# schemat.net
KiCad netlist of a schematic drawn in Altium Designer
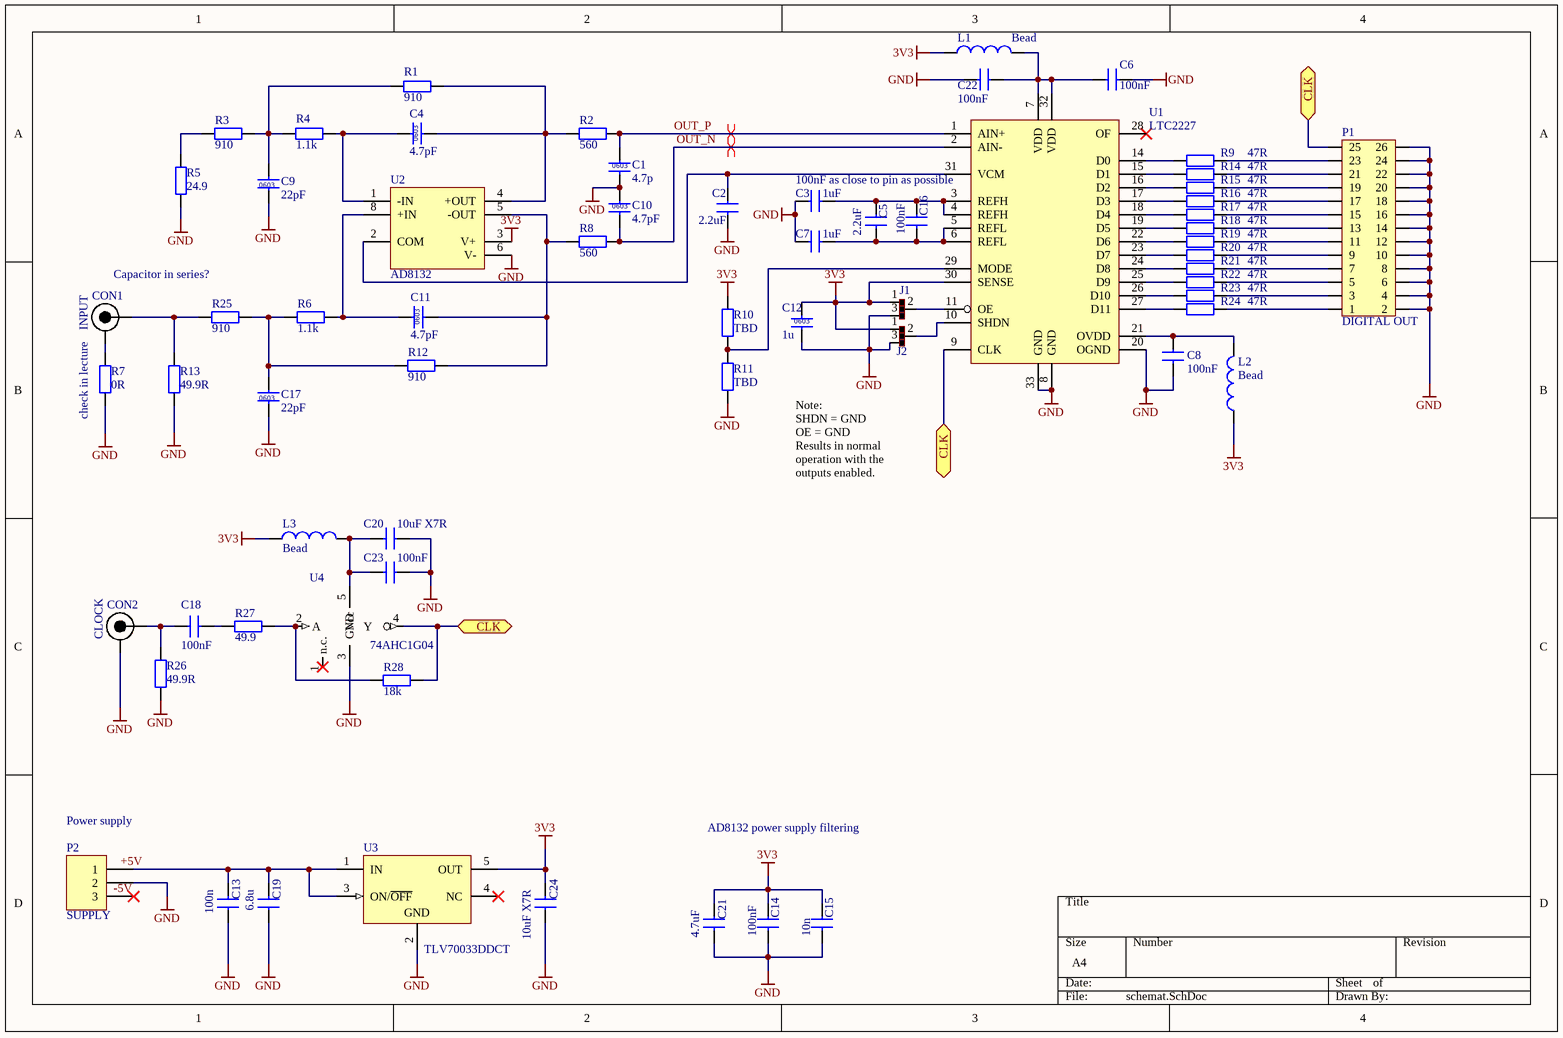
[diagram p0: schemat.SchDoc]

(export (version "E")
  (design (tool "Eeschema 10.0.6"))
  (components
    (comp (ref "C1")
      (value "4.7p")
      (footprint "0603")
      (fields (field (name "OBUDOWA") "0603"))
      (libsource (lib "iMX6") (part "Kondensator ceramiczny"))
    )
    (comp (ref "C2")
      (value "2.2uF")
      (footprint "0603")
      (libsource (lib "iMX6") (part "Kondensator ceramiczny"))
    )
    (comp (ref "C3")
      (value "1uF")
      (footprint "0603")
      (libsource (lib "iMX6") (part "Kondensator ceramiczny"))
    )
    (comp (ref "C4")
      (value "4.7pF")
      (footprint "0603")
      (fields (field (name "OBUDOWA") "0603"))
      (libsource (lib "iMX6") (part "Kondensator ceramiczny"))
    )
    (comp (ref "C5")
      (value "2.2uF")
      (footprint "0603")
      (libsource (lib "iMX6") (part "Kondensator ceramiczny"))
    )
    (comp (ref "C6")
      (value "100nF")
      (footprint "0603")
      (libsource (lib "iMX6") (part "Kondensator ceramiczny"))
    )
    (comp (ref "C7")
      (value "1uF")
      (footprint "0603")
      (libsource (lib "iMX6") (part "Kondensator ceramiczny"))
    )
    (comp (ref "C8")
      (value "100nF")
      (footprint "0603")
      (libsource (lib "iMX6") (part "Kondensator ceramiczny"))
    )
    (comp (ref "C9")
      (value "22pF")
      (footprint "0603")
      (fields (field (name "OBUDOWA") "0603"))
      (libsource (lib "iMX6") (part "Kondensator ceramiczny"))
    )
    (comp (ref "C10")
      (value "4.7pF")
      (footprint "0603")
      (fields (field (name "OBUDOWA") "0603"))
      (libsource (lib "iMX6") (part "Kondensator ceramiczny"))
    )
    (comp (ref "C11")
      (value "4.7pF")
      (footprint "0603")
      (fields (field (name "OBUDOWA") "0603"))
      (libsource (lib "iMX6") (part "Kondensator ceramiczny"))
    )
    (comp (ref "C12")
      (value "1u")
      (footprint "0603")
      (fields (field (name "OBUDOWA") "0603"))
      (libsource (lib "iMX6") (part "Kondensator ceramiczny"))
    )
    (comp (ref "C13")
      (value "100n")
      (footprint "0603")
      (libsource (lib "iMX6") (part "Kondensator ceramiczny"))
    )
    (comp (ref "C14")
      (value "100nF")
      (footprint "0603")
      (libsource (lib "iMX6") (part "Kondensator ceramiczny"))
    )
    (comp (ref "C15")
      (value "10n")
      (footprint "0603")
      (libsource (lib "iMX6") (part "Kondensator ceramiczny"))
    )
    (comp (ref "C16")
      (value "100nF")
      (footprint "0603")
      (libsource (lib "iMX6") (part "Kondensator ceramiczny"))
    )
    (comp (ref "C17")
      (value "22pF")
      (footprint "0603")
      (fields (field (name "OBUDOWA") "0603"))
      (libsource (lib "iMX6") (part "Kondensator ceramiczny"))
    )
    (comp (ref "C18")
      (value "100nF")
      (footprint "C0603")
      (libsource (lib "iMX6") (part "Kondensator ceramiczny"))
    )
    (comp (ref "C19")
      (value "6.8u")
      (footprint "0805")
      (libsource (lib "iMX6") (part "Kondensator ceramiczny"))
    )
    (comp (ref "C20")
      (value "10uF X7R")
      (footprint "0805")
      (libsource (lib "iMX6") (part "Kondensator ceramiczny"))
    )
    (comp (ref "C21")
      (value "4.7uF")
      (footprint "0603")
      (libsource (lib "iMX6") (part "Kondensator ceramiczny"))
    )
    (comp (ref "C22")
      (value "100nF")
      (footprint "0603")
      (libsource (lib "iMX6") (part "Kondensator ceramiczny"))
    )
    (comp (ref "C23")
      (value "100nF")
      (footprint "0603")
      (libsource (lib "iMX6") (part "Kondensator ceramiczny"))
    )
    (comp (ref "C24")
      (value "10uF X7R")
      (footprint "0805")
      (libsource (lib "iMX6") (part "Kondensator ceramiczny"))
    )
    (comp (ref "CON1") (value "INPUT") (footprint "SMA-16") (libsource (lib "A4WP") (part "SMA")))
    (comp (ref "CON2") (value "CLOCK") (footprint "SMA-16") (libsource (lib "A4WP") (part "SMA")))
    (comp (ref "J1") (value "ZW2/1") (footprint "ZW2/1") (libsource (lib "iMX6") (part "ZW2/1")))
    (comp (ref "J2") (value "ZW2/1") (footprint "ZW2/1") (libsource (lib "iMX6") (part "ZW2/1")))
    (comp (ref "L1")
      (value "Bead")
      (footprint "R0603")
      (description "Inductor")
      (fields (field (name "PUBLISHER") "Altium Limited"))
      (libsource (lib "Miscellaneous Devices") (part "Inductor"))
    )
    (comp (ref "L2")
      (value "Bead")
      (footprint "R0603")
      (description "Inductor")
      (fields (field (name "PUBLISHER") "Altium Limited"))
      (libsource (lib "Miscellaneous Devices") (part "Inductor"))
    )
    (comp (ref "L3")
      (value "Bead")
      (footprint "R0603")
      (description "Inductor")
      (fields (field (name "PUBLISHER") "Altium Limited"))
      (libsource (lib "Miscellaneous Devices") (part "Inductor"))
    )
    (comp (ref "P1")
      (value "DIGITAL OUT")
      (footprint "Header2x13")
      (libsource (lib "BibliotekiAltium") (part "Header2x13"))
    )
    (comp (ref "P2")
      (value "SUPPLY")
      (footprint "HDR1X3")
      (description "Header, 3-Pin")
      (fields (field (name "PUBLISHER") "Altium Limited"))
      (libsource (lib "Miscellaneous Connectors") (part "Header 3"))
    )
    (comp (ref "R1") (value "910") (footprint "0603") (libsource (lib "") (part "Rezystor_2")))
    (comp (ref "R2") (value "560") (footprint "0603") (libsource (lib "") (part "Rezystor_2")))
    (comp (ref "R3") (value "910") (footprint "0603") (libsource (lib "") (part "Rezystor_2")))
    (comp (ref "R4") (value "1.1k") (footprint "0603") (libsource (lib "") (part "Rezystor_2")))
    (comp (ref "R5") (value "24.9") (footprint "0603") (libsource (lib "") (part "Rezystor_1")))
    (comp (ref "R6") (value "1.1k") (footprint "0603") (libsource (lib "") (part "Rezystor_2")))
    (comp (ref "R7") (value "0R") (footprint "0603") (libsource (lib "") (part "Rezystor_1")))
    (comp (ref "R8") (value "560") (footprint "0603") (libsource (lib "") (part "Rezystor_2")))
    (comp (ref "R9") (value "47R") (footprint "0603") (libsource (lib "iMX6") (part "Rezystor")))
    (comp (ref "R10") (value "TBD") (footprint "0603") (libsource (lib "") (part "Rezystor_1")))
    (comp (ref "R11") (value "TBD") (footprint "0603") (libsource (lib "") (part "Rezystor_1")))
    (comp (ref "R12") (value "910") (footprint "0603CW") (libsource (lib "iMX6") (part "Rezystor")))
    (comp (ref "R13") (value "49.9R") (footprint "0603") (libsource (lib "") (part "Rezystor_1")))
    (comp (ref "R14") (value "47R") (footprint "0603") (libsource (lib "iMX6") (part "Rezystor")))
    (comp (ref "R15") (value "47R") (footprint "0603") (libsource (lib "iMX6") (part "Rezystor")))
    (comp (ref "R16") (value "47R") (footprint "0603") (libsource (lib "iMX6") (part "Rezystor")))
    (comp (ref "R17") (value "47R") (footprint "0603") (libsource (lib "iMX6") (part "Rezystor")))
    (comp (ref "R18") (value "47R") (footprint "0603") (libsource (lib "iMX6") (part "Rezystor")))
    (comp (ref "R19") (value "47R") (footprint "0603") (libsource (lib "iMX6") (part "Rezystor")))
    (comp (ref "R20") (value "47R") (footprint "0603") (libsource (lib "iMX6") (part "Rezystor")))
    (comp (ref "R21") (value "47R") (footprint "0603") (libsource (lib "iMX6") (part "Rezystor")))
    (comp (ref "R22") (value "47R") (footprint "0603") (libsource (lib "iMX6") (part "Rezystor")))
    (comp (ref "R23") (value "47R") (footprint "0603") (libsource (lib "iMX6") (part "Rezystor")))
    (comp (ref "R24") (value "47R") (footprint "0603") (libsource (lib "iMX6") (part "Rezystor")))
    (comp (ref "R25") (value "910") (footprint "0603") (libsource (lib "iMX6") (part "Rezystor")))
    (comp (ref "R26") (value "49.9R") (footprint "0603") (libsource (lib "") (part "Rezystor_1")))
    (comp (ref "R27") (value "49.9") (footprint "R0603") (libsource (lib "iMX6") (part "Rezystor")))
    (comp (ref "R28") (value "18k") (footprint "R0603") (libsource (lib "iMX6") (part "Rezystor")))
    (comp (ref "U1") (value "LTC2227") (footprint "QFN32") (libsource (lib "ADC") (part "LTC222x")))
    (comp (ref "U2")
      (value "AD8132")
      (footprint "SOIC8")
      (libsource (lib "BibliotekiAltium") (part "AD8132"))
    )
    (comp (ref "U3")
      (value "TLV70033DDCT")
      (footprint "SOT23-5")
      (description "Micropower 50 mA Ultra Low-Dropout Regulator, 5-pin SOT-23")
      (fields
        (field (name "PARTNUMBER") "LP2980AIM5-3.3")
        (field (name "MANUFACTURER") "National Semiconductor")
        (field (name "PUBLISHER") "Altium Limited")
      )
      (libsource (lib "NSC LDO") (part "LP2980AIM5-3.3"))
    )
    (comp (ref "U4")
      (value "74AHC1G04")
      (footprint "TSSOP5 (SOT353-1)")
      (description "74AHC1G04 and 74AHCT1G04 are high-speed Si-gate CMOS devices. They provide an  inverting buffer.")
      (libsource (lib "Gates") (part "74AHC1G04"))
    )
  )
  (nets
    (net (code "3") (name "/CLK") (class "Default")
      (node (ref "P1") (pin "25") (pinfunction "25_25") (pintype "passive"))
      (node (ref "R28") (pin "1") (pinfunction "1_1") (pintype "passive"))
      (node (ref "U1") (pin "9") (pinfunction "CLK_9") (pintype "power_in"))
      (node (ref "U4") (pin "4") (pinfunction "Y_4") (pintype "output"))
    )
    (net (code "4") (name "/OUT_N") (class "Default")
      (node (ref "C10") (pin "2") (pinfunction "2_2") (pintype "passive"))
      (node (ref "R8") (pin "2") (pinfunction "2_2") (pintype "passive"))
      (node (ref "U1") (pin "2") (pinfunction "AIN-_2") (pintype "power_in"))
    )
    (net (code "5") (name "/OUT_P") (class "Default")
      (node (ref "C1") (pin "1") (pinfunction "1_1") (pintype "passive"))
      (node (ref "R2") (pin "2") (pinfunction "2_2") (pintype "passive"))
      (node (ref "U1") (pin "1") (pinfunction "AIN+_1") (pintype "power_in"))
    )
    (net (code "6") (name "3V3") (class "Default")
      (node (ref "C12") (pin "1") (pinfunction "1_1") (pintype "passive"))
      (node (ref "C14") (pin "2") (pinfunction "2_2") (pintype "passive"))
      (node (ref "C15") (pin "2") (pinfunction "2_2") (pintype "passive"))
      (node (ref "C21") (pin "1") (pinfunction "1_1") (pintype "passive"))
      (node (ref "C24") (pin "1") (pinfunction "1_1") (pintype "passive"))
      (node (ref "J1") (pin "1") (pinfunction "SW2_1") (pintype "passive"))
      (node (ref "J2") (pin "1") (pinfunction "SW2_1") (pintype "passive"))
      (node (ref "L1") (pin "1") (pinfunction "1_1") (pintype "passive"))
      (node (ref "L2") (pin "1") (pinfunction "1_1") (pintype "passive"))
      (node (ref "L3") (pin "1") (pinfunction "1_1") (pintype "passive"))
      (node (ref "R10") (pin "2") (pinfunction "2_2") (pintype "passive"))
      (node (ref "U1") (pin "30") (pinfunction "SENSE_30") (pintype "power_in"))
      (node (ref "U2") (pin "3") (pinfunction "V+_3") (pintype "passive"))
      (node (ref "U3") (pin "5") (pinfunction "OUT_5") (pintype "power_in"))
    )
    (net (code "7") (name "GND") (class "Default")
      (node (ref "C1") (pin "2") (pinfunction "2_2") (pintype "passive"))
      (node (ref "C10") (pin "1") (pinfunction "1_1") (pintype "passive"))
      (node (ref "C12") (pin "2") (pinfunction "2_2") (pintype "passive"))
      (node (ref "C13") (pin "2") (pinfunction "2_2") (pintype "passive"))
      (node (ref "C14") (pin "1") (pinfunction "1_1") (pintype "passive"))
      (node (ref "C15") (pin "1") (pinfunction "1_1") (pintype "passive"))
      (node (ref "C17") (pin "1") (pinfunction "1_1") (pintype "passive"))
      (node (ref "C19") (pin "2") (pinfunction "2_2") (pintype "passive"))
      (node (ref "C2") (pin "2") (pinfunction "2_2") (pintype "passive"))
      (node (ref "C20") (pin "2") (pinfunction "2_2") (pintype "passive"))
      (node (ref "C21") (pin "2") (pinfunction "2_2") (pintype "passive"))
      (node (ref "C22") (pin "2") (pinfunction "2_2") (pintype "passive"))
      (node (ref "C23") (pin "1") (pinfunction "1_1") (pintype "passive"))
      (node (ref "C24") (pin "2") (pinfunction "2_2") (pintype "passive"))
      (node (ref "C3") (pin "1") (pinfunction "1_1") (pintype "passive"))
      (node (ref "C6") (pin "1") (pinfunction "1_1") (pintype "passive"))
      (node (ref "C7") (pin "2") (pinfunction "2_2") (pintype "passive"))
      (node (ref "C8") (pin "1") (pinfunction "1_1") (pintype "passive"))
      (node (ref "C9") (pin "1") (pinfunction "1_1") (pintype "passive"))
      (node (ref "CON2") (pin "1") (pinfunction "1_1") (pintype "passive"))
      (node (ref "J1") (pin "3") (pinfunction "SW4_3") (pintype "passive"))
      (node (ref "J2") (pin "3") (pinfunction "SW4_3") (pintype "passive"))
      (node (ref "P1") (pin "10") (pinfunction "10_10") (pintype "passive"))
      (node (ref "P1") (pin "12") (pinfunction "12_12") (pintype "passive"))
      (node (ref "P1") (pin "14") (pinfunction "14_14") (pintype "passive"))
      (node (ref "P1") (pin "16") (pinfunction "16_16") (pintype "passive"))
      (node (ref "P1") (pin "18") (pinfunction "18_18") (pintype "passive"))
      (node (ref "P1") (pin "2") (pinfunction "2_2") (pintype "passive"))
      (node (ref "P1") (pin "20") (pinfunction "20_20") (pintype "passive"))
      (node (ref "P1") (pin "22") (pinfunction "22_22") (pintype "passive"))
      (node (ref "P1") (pin "24") (pinfunction "24_24") (pintype "passive"))
      (node (ref "P1") (pin "26") (pinfunction "26_26") (pintype "passive"))
      (node (ref "P1") (pin "4") (pinfunction "4_4") (pintype "passive"))
      (node (ref "P1") (pin "6") (pinfunction "6_6") (pintype "passive"))
      (node (ref "P1") (pin "8") (pinfunction "8_8") (pintype "passive"))
      (node (ref "P2") (pin "2") (pinfunction "2_2") (pintype "passive"))
      (node (ref "R11") (pin "1") (pinfunction "1_1") (pintype "passive"))
      (node (ref "R13") (pin "1") (pinfunction "1_1") (pintype "passive"))
      (node (ref "R26") (pin "1") (pinfunction "1_1") (pintype "passive"))
      (node (ref "R5") (pin "1") (pinfunction "1_1") (pintype "passive"))
      (node (ref "R7") (pin "1") (pinfunction "1_1") (pintype "passive"))
      (node (ref "U1") (pin "20") (pinfunction "OGND_20") (pintype "power_in"))
      (node (ref "U1") (pin "33") (pinfunction "GND_33") (pintype "power_in"))
      (node (ref "U1") (pin "8") (pinfunction "GND_8") (pintype "power_in"))
      (node (ref "U2") (pin "6") (pinfunction "V-_6") (pintype "passive"))
      (node (ref "U3") (pin "2") (pinfunction "GND_2") (pintype "power_in"))
      (node (ref "U4") (pin "3") (pinfunction "GND_3") (pintype "power_in"))
    )
    (net (code "8") (name "Net-(C9-Pad2)") (class "Default")
      (node (ref "C9") (pin "2") (pinfunction "2_2") (pintype "passive"))
      (node (ref "R1") (pin "1") (pinfunction "1_1") (pintype "passive"))
      (node (ref "R3") (pin "2") (pinfunction "2_2") (pintype "passive"))
      (node (ref "R4") (pin "1") (pinfunction "1_1") (pintype "passive"))
    )
    (net (code "9") (name "Net-(C16-Pad1)") (class "Default")
      (node (ref "C16") (pin "1") (pinfunction "1_1") (pintype "passive"))
      (node (ref "C5") (pin "2") (pinfunction "2_2") (pintype "passive"))
      (node (ref "C7") (pin "1") (pinfunction "1_1") (pintype "passive"))
      (node (ref "U1") (pin "5") (pinfunction "REFL_5") (pintype "power_in"))
      (node (ref "U1") (pin "6") (pinfunction "REFL_6") (pintype "power_in"))
    )
    (net (code "10") (name "Net-(C16-Pad2)") (class "Default")
      (node (ref "C16") (pin "2") (pinfunction "2_2") (pintype "passive"))
      (node (ref "C3") (pin "2") (pinfunction "2_2") (pintype "passive"))
      (node (ref "C5") (pin "1") (pinfunction "1_1") (pintype "passive"))
      (node (ref "U1") (pin "3") (pinfunction "REFH_3") (pintype "power_in"))
      (node (ref "U1") (pin "4") (pinfunction "REFH_4") (pintype "power_in"))
    )
    (net (code "11") (name "Net-(C17-Pad2)") (class "Default")
      (node (ref "C17") (pin "2") (pinfunction "2_2") (pintype "passive"))
      (node (ref "R12") (pin "2") (pinfunction "2_2") (pintype "passive"))
      (node (ref "R25") (pin "1") (pinfunction "1_1") (pintype "passive"))
      (node (ref "R6") (pin "1") (pinfunction "1_1") (pintype "passive"))
    )
    (net (code "12") (name "Net-(C18-Pad1)") (class "Default")
      (node (ref "C18") (pin "1") (pinfunction "1_1") (pintype "passive"))
      (node (ref "R27") (pin "2") (pinfunction "2_2") (pintype "passive"))
    )
    (net (code "13") (name "Net-(C18-Pad2)") (class "Default")
      (node (ref "C18") (pin "2") (pinfunction "2_2") (pintype "passive"))
      (node (ref "CON2") (pin "2") (pinfunction "2_2") (pintype "passive"))
      (node (ref "R26") (pin "2") (pinfunction "2_2") (pintype "passive"))
    )
    (net (code "14") (name "Net-(C22-Pad1)") (class "Default")
      (node (ref "C22") (pin "1") (pinfunction "1_1") (pintype "passive"))
      (node (ref "C6") (pin "2") (pinfunction "2_2") (pintype "passive"))
      (node (ref "L1") (pin "2") (pinfunction "2_2") (pintype "passive"))
      (node (ref "U1") (pin "32") (pinfunction "VDD_32") (pintype "power_in"))
      (node (ref "U1") (pin "7") (pinfunction "VDD_7") (pintype "power_in"))
    )
    (net (code "15") (name "Net-(CON1-Pad1)") (class "Default")
      (node (ref "CON1") (pin "1") (pinfunction "1_1") (pintype "passive"))
      (node (ref "R7") (pin "2") (pinfunction "2_2") (pintype "passive"))
    )
    (net (code "16") (name "Net-(CON1-Pad2)") (class "Default")
      (node (ref "CON1") (pin "2") (pinfunction "2_2") (pintype "passive"))
      (node (ref "R13") (pin "2") (pinfunction "2_2") (pintype "passive"))
      (node (ref "R25") (pin "2") (pinfunction "2_2") (pintype "passive"))
    )
    (net (code "17") (name "Net-(J1-SW3)") (class "Default")
      (node (ref "J1") (pin "2") (pinfunction "SW3_2") (pintype "passive"))
      (node (ref "U1") (pin "11") (pinfunction "OE_11") (pintype "power_in"))
    )
    (net (code "18") (name "Net-(J2-SW3)") (class "Default")
      (node (ref "J2") (pin "2") (pinfunction "SW3_2") (pintype "passive"))
      (node (ref "U1") (pin "10") (pinfunction "SHDN_10") (pintype "power_in"))
    )
    (net (code "19") (name "Net-(P1-Pad1)") (class "Default")
      (node (ref "P1") (pin "1") (pinfunction "1_1") (pintype "passive"))
      (node (ref "R24") (pin "1") (pinfunction "1_1") (pintype "passive"))
    )
    (net (code "20") (name "Net-(P1-Pad3)") (class "Default")
      (node (ref "P1") (pin "3") (pinfunction "3_3") (pintype "passive"))
      (node (ref "R23") (pin "1") (pinfunction "1_1") (pintype "passive"))
    )
    (net (code "21") (name "Net-(P1-Pad5)") (class "Default")
      (node (ref "P1") (pin "5") (pinfunction "5_5") (pintype "passive"))
      (node (ref "R22") (pin "1") (pinfunction "1_1") (pintype "passive"))
    )
    (net (code "22") (name "Net-(P1-Pad7)") (class "Default")
      (node (ref "P1") (pin "7") (pinfunction "7_7") (pintype "passive"))
      (node (ref "R21") (pin "1") (pinfunction "1_1") (pintype "passive"))
    )
    (net (code "23") (name "Net-(P1-Pad9)") (class "Default")
      (node (ref "P1") (pin "9") (pinfunction "9_9") (pintype "passive"))
      (node (ref "R20") (pin "1") (pinfunction "1_1") (pintype "passive"))
    )
    (net (code "24") (name "Net-(P1-Pad11)") (class "Default")
      (node (ref "P1") (pin "11") (pinfunction "11_11") (pintype "passive"))
      (node (ref "R19") (pin "1") (pinfunction "1_1") (pintype "passive"))
    )
    (net (code "25") (name "Net-(P1-Pad13)") (class "Default")
      (node (ref "P1") (pin "13") (pinfunction "13_13") (pintype "passive"))
      (node (ref "R18") (pin "1") (pinfunction "1_1") (pintype "passive"))
    )
    (net (code "26") (name "Net-(P1-Pad15)") (class "Default")
      (node (ref "P1") (pin "15") (pinfunction "15_15") (pintype "passive"))
      (node (ref "R17") (pin "1") (pinfunction "1_1") (pintype "passive"))
    )
    (net (code "27") (name "Net-(P1-Pad17)") (class "Default")
      (node (ref "P1") (pin "17") (pinfunction "17_17") (pintype "passive"))
      (node (ref "R16") (pin "1") (pinfunction "1_1") (pintype "passive"))
    )
    (net (code "28") (name "Net-(P1-Pad19)") (class "Default")
      (node (ref "P1") (pin "19") (pinfunction "19_19") (pintype "passive"))
      (node (ref "R15") (pin "1") (pinfunction "1_1") (pintype "passive"))
    )
    (net (code "29") (name "Net-(P1-Pad21)") (class "Default")
      (node (ref "P1") (pin "21") (pinfunction "21_21") (pintype "passive"))
      (node (ref "R14") (pin "1") (pinfunction "1_1") (pintype "passive"))
    )
    (net (code "30") (name "Net-(P1-Pad23)") (class "Default")
      (node (ref "P1") (pin "23") (pinfunction "23_23") (pintype "passive"))
      (node (ref "R9") (pin "1") (pinfunction "1_1") (pintype "passive"))
    )
    (net (code "31") (name "Net-(R3-Pad1)") (class "Default")
      (node (ref "R3") (pin "1") (pinfunction "1_1") (pintype "passive"))
      (node (ref "R5") (pin "2") (pinfunction "2_2") (pintype "passive"))
    )
    (net (code "32") (name "Net-(U1-D0)") (class "Default")
      (node (ref "R9") (pin "2") (pinfunction "2_2") (pintype "passive"))
      (node (ref "U1") (pin "14") (pinfunction "D0_14") (pintype "power_in"))
    )
    (net (code "33") (name "Net-(U1-D1)") (class "Default")
      (node (ref "R14") (pin "2") (pinfunction "2_2") (pintype "passive"))
      (node (ref "U1") (pin "15") (pinfunction "D1_15") (pintype "power_in"))
    )
    (net (code "34") (name "Net-(U1-D2)") (class "Default")
      (node (ref "R15") (pin "2") (pinfunction "2_2") (pintype "passive"))
      (node (ref "U1") (pin "16") (pinfunction "D2_16") (pintype "power_in"))
    )
    (net (code "35") (name "Net-(U1-D3)") (class "Default")
      (node (ref "R16") (pin "2") (pinfunction "2_2") (pintype "passive"))
      (node (ref "U1") (pin "17") (pinfunction "D3_17") (pintype "power_in"))
    )
    (net (code "36") (name "Net-(U1-D4)") (class "Default")
      (node (ref "R17") (pin "2") (pinfunction "2_2") (pintype "passive"))
      (node (ref "U1") (pin "18") (pinfunction "D4_18") (pintype "power_in"))
    )
    (net (code "37") (name "Net-(U1-D5)") (class "Default")
      (node (ref "R18") (pin "2") (pinfunction "2_2") (pintype "passive"))
      (node (ref "U1") (pin "19") (pinfunction "D5_19") (pintype "power_in"))
    )
    (net (code "38") (name "Net-(U1-D6)") (class "Default")
      (node (ref "R19") (pin "2") (pinfunction "2_2") (pintype "passive"))
      (node (ref "U1") (pin "22") (pinfunction "D6_22") (pintype "power_in"))
    )
    (net (code "39") (name "Net-(U1-D7)") (class "Default")
      (node (ref "R20") (pin "2") (pinfunction "2_2") (pintype "passive"))
      (node (ref "U1") (pin "23") (pinfunction "D7_23") (pintype "power_in"))
    )
    (net (code "40") (name "Net-(U1-D8)") (class "Default")
      (node (ref "R21") (pin "2") (pinfunction "2_2") (pintype "passive"))
      (node (ref "U1") (pin "24") (pinfunction "D8_24") (pintype "power_in"))
    )
    (net (code "41") (name "Net-(U1-D9)") (class "Default")
      (node (ref "R22") (pin "2") (pinfunction "2_2") (pintype "passive"))
      (node (ref "U1") (pin "25") (pinfunction "D9_25") (pintype "power_in"))
    )
    (net (code "42") (name "Net-(U1-D10)") (class "Default")
      (node (ref "R23") (pin "2") (pinfunction "2_2") (pintype "passive"))
      (node (ref "U1") (pin "26") (pinfunction "D10_26") (pintype "power_in"))
    )
    (net (code "43") (name "Net-(U1-D11)") (class "Default")
      (node (ref "R24") (pin "2") (pinfunction "2_2") (pintype "passive"))
      (node (ref "U1") (pin "27") (pinfunction "D11_27") (pintype "power_in"))
    )
    (net (code "44") (name "Net-(U1-MODE)") (class "Default")
      (node (ref "R10") (pin "1") (pinfunction "1_1") (pintype "passive"))
      (node (ref "R11") (pin "2") (pinfunction "2_2") (pintype "passive"))
      (node (ref "U1") (pin "29") (pinfunction "MODE_29") (pintype "power_in"))
    )
    (net (code "45") (name "Net-(U1-OVDD)") (class "Default")
      (node (ref "C8") (pin "2") (pinfunction "2_2") (pintype "passive"))
      (node (ref "L2") (pin "2") (pinfunction "2_2") (pintype "passive"))
      (node (ref "U1") (pin "21") (pinfunction "OVDD_21") (pintype "power_in"))
    )
    (net (code "46") (name "Net-(U1-VCM)") (class "Default")
      (node (ref "C2") (pin "1") (pinfunction "1_1") (pintype "passive"))
      (node (ref "U1") (pin "31") (pinfunction "VCM_31") (pintype "power_in"))
      (node (ref "U2") (pin "2") (pinfunction "COM_2") (pintype "passive"))
    )
    (net (code "47") (name "Net-(U2-+IN)") (class "Default")
      (node (ref "C11") (pin "1") (pinfunction "1_1") (pintype "passive"))
      (node (ref "R6") (pin "2") (pinfunction "2_2") (pintype "passive"))
      (node (ref "U2") (pin "8") (pinfunction "+IN_8") (pintype "passive"))
    )
    (net (code "48") (name "Net-(U2-+OUT)") (class "Default")
      (node (ref "C4") (pin "2") (pinfunction "2_2") (pintype "passive"))
      (node (ref "R1") (pin "2") (pinfunction "2_2") (pintype "passive"))
      (node (ref "R2") (pin "1") (pinfunction "1_1") (pintype "passive"))
      (node (ref "U2") (pin "4") (pinfunction "+OUT_4") (pintype "passive"))
    )
    (net (code "49") (name "Net-(U2--IN)") (class "Default")
      (node (ref "C4") (pin "1") (pinfunction "1_1") (pintype "passive"))
      (node (ref "R4") (pin "2") (pinfunction "2_2") (pintype "passive"))
      (node (ref "U2") (pin "1") (pinfunction "-IN_1") (pintype "passive"))
    )
    (net (code "50") (name "Net-(U2--OUT)") (class "Default")
      (node (ref "C11") (pin "2") (pinfunction "2_2") (pintype "passive"))
      (node (ref "R12") (pin "1") (pinfunction "1_1") (pintype "passive"))
      (node (ref "R8") (pin "1") (pinfunction "1_1") (pintype "passive"))
      (node (ref "U2") (pin "5") (pinfunction "-OUT_5") (pintype "passive"))
    )
    (net (code "51") (name "Net-(U3-IN)") (class "Default")
      (node (ref "C13") (pin "1") (pinfunction "1_1") (pintype "passive"))
      (node (ref "C19") (pin "1") (pinfunction "1_1") (pintype "passive"))
      (node (ref "P2") (pin "1") (pinfunction "1_1") (pintype "passive"))
      (node (ref "U3") (pin "1") (pinfunction "IN_1") (pintype "power_in"))
      (node (ref "U3") (pin "3") (pinfunction "ON/~{OFF}_3") (pintype "input"))
    )
    (net (code "52") (name "Net-(U4-A)") (class "Default")
      (node (ref "R27") (pin "1") (pinfunction "1_1") (pintype "passive"))
      (node (ref "R28") (pin "2") (pinfunction "2_2") (pintype "passive"))
      (node (ref "U4") (pin "2") (pinfunction "A_2") (pintype "input"))
    )
    (net (code "53") (name "Net-(U4-Vcc)") (class "Default")
      (node (ref "C20") (pin "1") (pinfunction "1_1") (pintype "passive"))
      (node (ref "C23") (pin "2") (pinfunction "2_2") (pintype "passive"))
      (node (ref "L3") (pin "2") (pinfunction "2_2") (pintype "passive"))
      (node (ref "U4") (pin "5") (pinfunction "Vcc_5") (pintype "passive"))
    )
    (net (code "54") (name "unconnected-(P2-Pad3)") (class "Default")
      (node (ref "P2") (pin "3") (pinfunction "3_3") (pintype "passive+no_connect"))
    )
    (net (code "55") (name "unconnected-(U1-OF-Pad28)") (class "Default")
      (node (ref "U1") (pin "28") (pinfunction "OF_28") (pintype "power_in+no_connect"))
    )
    (net (code "56") (name "unconnected-(U3-NC-Pad4)") (class "Default")
      (node (ref "U3") (pin "4") (pinfunction "NC_4") (pintype "passive+no_connect"))
    )
    (net (code "57") (name "unconnected-(U4-n.c.-Pad1)") (class "Default")
      (node (ref "U4") (pin "1") (pinfunction "n.c._1") (pintype "passive+no_connect"))
    )
  )
)
